# gpio_led.net
KiCad netlist of a schematic drawn in Altium Designer
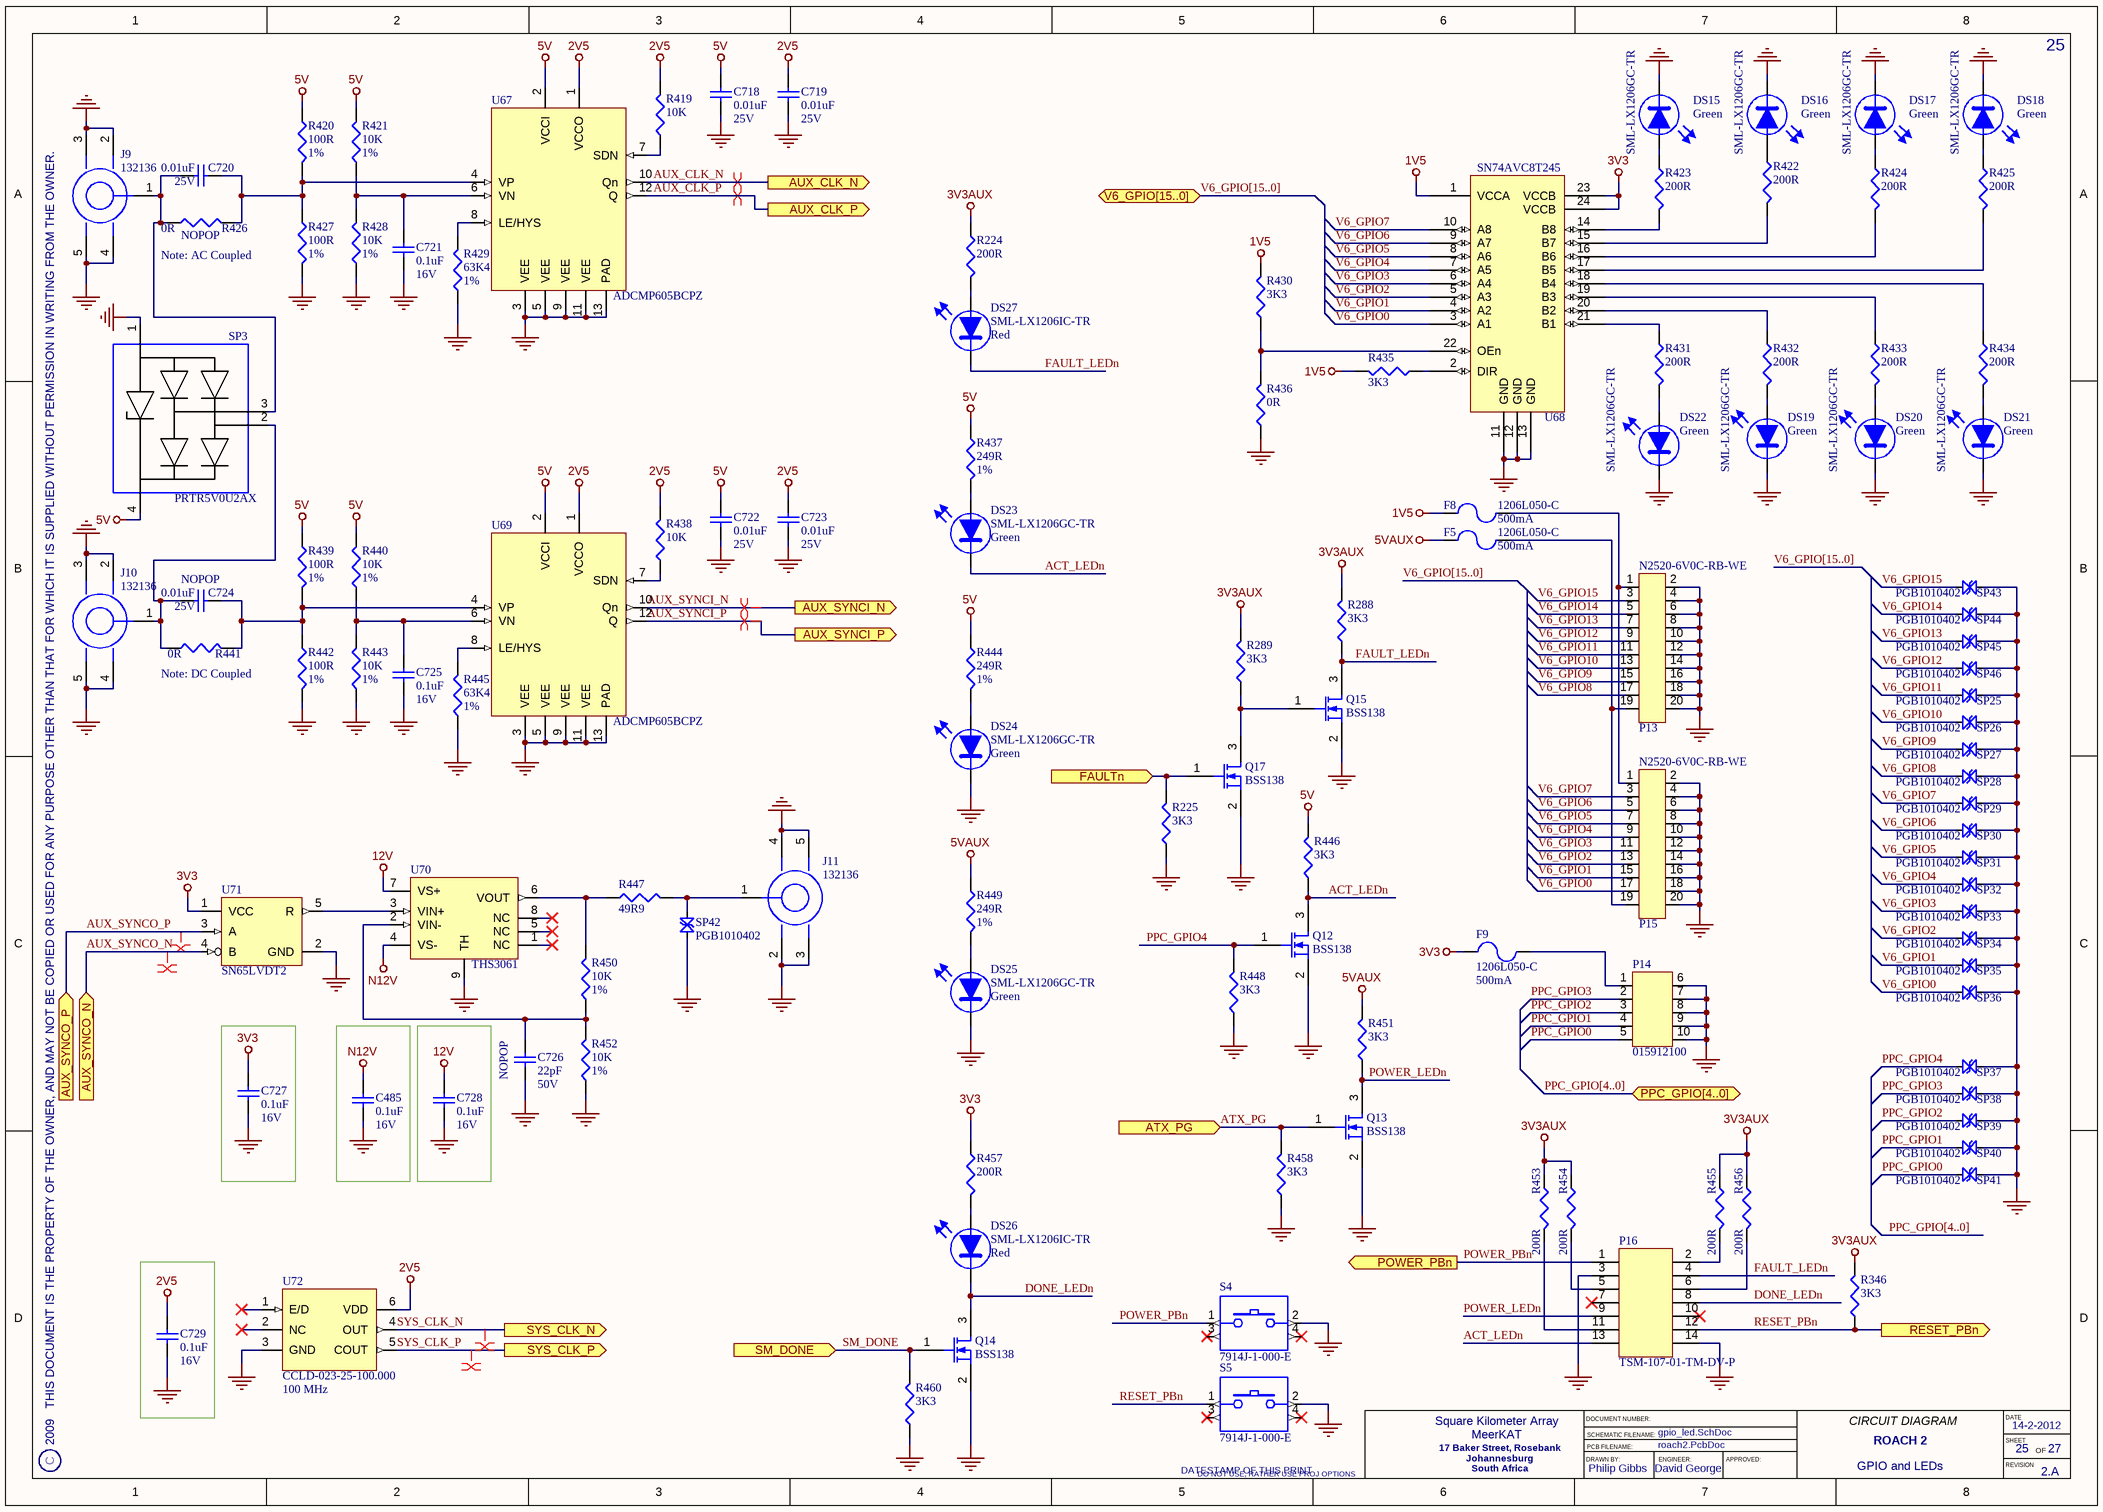
[diagram p0: gpio_led.SchDoc]

(export (version "E")
  (design (tool "Eeschema 10.0.6"))
  (components
    (comp (ref "C485")
      (value "0.1uF")
      (footprint "CAPC1005X60L")
      (description "0.1uF, Ceramic Capacitor")
      (fields
        (field (name "RATING") "16V")
        (field (name "MANUFACTURER") "VENKEL")
        (field (name "PARTNUM") "C0402X7R160-104KN")
      )
      (libsource (lib "altium_db") (part "CapStd"))
    )
    (comp (ref "C718")
      (value "0.01uF")
      (footprint "CAPC1005X55L")
      (description "0.01uF, Ceramic Capacitor")
      (fields
        (field (name "RATING") "25V")
        (field (name "MANUFACTURER") "MURATA")
        (field (name "PARTNUM") "GRM155R71E103KA01D")
      )
      (libsource (lib "altium_db") (part "CapStd"))
    )
    (comp (ref "C719")
      (value "0.01uF")
      (footprint "CAPC1005X55L")
      (description "0.01uF, Ceramic Capacitor")
      (fields
        (field (name "RATING") "25V")
        (field (name "MANUFACTURER") "MURATA")
        (field (name "PARTNUM") "GRM155R71E103KA01D")
      )
      (libsource (lib "altium_db") (part "CapStd"))
    )
    (comp (ref "C720")
      (value "0.01uF")
      (footprint "CAPC1005X55L")
      (description "0.01uF, Ceramic Capacitor")
      (fields
        (field (name "RATING") "25V")
        (field (name "MANUFACTURER") "MURATA")
        (field (name "PARTNUM") "GRM155R71E103KA01D")
      )
      (libsource (lib "altium_db") (part "CapStd"))
    )
    (comp (ref "C721")
      (value "0.1uF")
      (footprint "CAPC1005X60L")
      (description "0.1uF, Ceramic Capacitor")
      (fields
        (field (name "RATING") "16V")
        (field (name "MANUFACTURER") "VENKEL")
        (field (name "PARTNUM") "C0402X7R160-104KN")
      )
      (libsource (lib "altium_db") (part "CapStd"))
    )
    (comp (ref "C722")
      (value "0.01uF")
      (footprint "CAPC1005X55L")
      (description "0.01uF, Ceramic Capacitor")
      (fields
        (field (name "RATING") "25V")
        (field (name "MANUFACTURER") "MURATA")
        (field (name "PARTNUM") "GRM155R71E103KA01D")
      )
      (libsource (lib "altium_db") (part "CapStd"))
    )
    (comp (ref "C723")
      (value "0.01uF")
      (footprint "CAPC1005X55L")
      (description "0.01uF, Ceramic Capacitor")
      (fields
        (field (name "RATING") "25V")
        (field (name "MANUFACTURER") "MURATA")
        (field (name "PARTNUM") "GRM155R71E103KA01D")
      )
      (libsource (lib "altium_db") (part "CapStd"))
    )
    (comp (ref "C724")
      (value "0.01uF")
      (footprint "CAPC1005X55L")
      (description "0.01uF, Ceramic Capacitor")
      (fields
        (field (name "RATING") "25V")
        (field (name "MANUFACTURER") "MURATA")
        (field (name "PARTNUM") "GRM155R71E103KA01D")
      )
      (libsource (lib "altium_db") (part "CapStd"))
    )
    (comp (ref "C725")
      (value "0.1uF")
      (footprint "CAPC1005X60L")
      (description "0.1uF, Ceramic Capacitor")
      (fields
        (field (name "RATING") "16V")
        (field (name "MANUFACTURER") "VENKEL")
        (field (name "PARTNUM") "C0402X7R160-104KN")
      )
      (libsource (lib "altium_db") (part "CapStd"))
    )
    (comp (ref "C726")
      (value "22pF")
      (footprint "CAPC1005X55L")
      (description "22pF, Ceramic Capacitor")
      (fields
        (field (name "RATING") "50V")
        (field (name "MANUFACTURER") "MURATA")
        (field (name "PARTNUM") "GRM1555C1H220JZ01D")
      )
      (libsource (lib "altium_db") (part "CapStd"))
    )
    (comp (ref "C727")
      (value "0.1uF")
      (footprint "CAPC1005X60L")
      (description "0.1uF, Ceramic Capacitor")
      (fields
        (field (name "RATING") "16V")
        (field (name "MANUFACTURER") "VENKEL")
        (field (name "PARTNUM") "C0402X7R160-104KN")
      )
      (libsource (lib "altium_db") (part "CapStd"))
    )
    (comp (ref "C728")
      (value "0.1uF")
      (footprint "CAPC1005X60L")
      (description "0.1uF, Ceramic Capacitor")
      (fields
        (field (name "RATING") "16V")
        (field (name "MANUFACTURER") "VENKEL")
        (field (name "PARTNUM") "C0402X7R160-104KN")
      )
      (libsource (lib "altium_db") (part "CapStd"))
    )
    (comp (ref "C729")
      (value "0.1uF")
      (footprint "CAPC1005X60L")
      (description "0.1uF, Ceramic Capacitor")
      (fields
        (field (name "RATING") "16V")
        (field (name "MANUFACTURER") "VENKEL")
        (field (name "PARTNUM") "C0402X7R160-104KN")
      )
      (libsource (lib "altium_db") (part "CapStd"))
    )
    (comp (ref "DS15")
      (value "SML-LX1206GC-TR")
      (footprint "LEDC3216X120N")
      (description "Green, Surface mount, LED, 1206")
      (fields (field (name "COLOUR") "Green") (field (name "MANUFACTURER") "LUMEX"))
      (libsource (lib "altium_db") (part "LEDSTD"))
    )
    (comp (ref "DS16")
      (value "SML-LX1206GC-TR")
      (footprint "LEDC3216X120N")
      (description "Green, Surface mount, LED, 1206")
      (fields (field (name "COLOUR") "Green") (field (name "MANUFACTURER") "LUMEX"))
      (libsource (lib "altium_db") (part "LEDSTD"))
    )
    (comp (ref "DS17")
      (value "SML-LX1206GC-TR")
      (footprint "LEDC3216X120N")
      (description "Green, Surface mount, LED, 1206")
      (fields (field (name "COLOUR") "Green") (field (name "MANUFACTURER") "LUMEX"))
      (libsource (lib "altium_db") (part "LEDSTD"))
    )
    (comp (ref "DS18")
      (value "SML-LX1206GC-TR")
      (footprint "LEDC3216X120N")
      (description "Green, Surface mount, LED, 1206")
      (fields (field (name "COLOUR") "Green") (field (name "MANUFACTURER") "LUMEX"))
      (libsource (lib "altium_db") (part "LEDSTD"))
    )
    (comp (ref "DS19")
      (value "SML-LX1206GC-TR")
      (footprint "LEDC3216X120N")
      (description "Green, Surface mount, LED, 1206")
      (fields (field (name "COLOUR") "Green") (field (name "MANUFACTURER") "LUMEX"))
      (libsource (lib "altium_db") (part "LEDSTD"))
    )
    (comp (ref "DS20")
      (value "SML-LX1206GC-TR")
      (footprint "LEDC3216X120N")
      (description "Green, Surface mount, LED, 1206")
      (fields (field (name "COLOUR") "Green") (field (name "MANUFACTURER") "LUMEX"))
      (libsource (lib "altium_db") (part "LEDSTD"))
    )
    (comp (ref "DS21")
      (value "SML-LX1206GC-TR")
      (footprint "LEDC3216X120N")
      (description "Green, Surface mount, LED, 1206")
      (fields (field (name "COLOUR") "Green") (field (name "MANUFACTURER") "LUMEX"))
      (libsource (lib "altium_db") (part "LEDSTD"))
    )
    (comp (ref "DS22")
      (value "SML-LX1206GC-TR")
      (footprint "LEDC3216X120N")
      (description "Green, Surface mount, LED, 1206")
      (fields (field (name "COLOUR") "Green") (field (name "MANUFACTURER") "LUMEX"))
      (libsource (lib "altium_db") (part "LEDSTD"))
    )
    (comp (ref "DS23")
      (value "SML-LX1206GC-TR")
      (footprint "LEDC3216X120N")
      (description "Green, Surface mount, LED, 1206")
      (fields (field (name "COLOUR") "Green") (field (name "MANUFACTURER") "LUMEX"))
      (libsource (lib "altium_db") (part "LEDSTD"))
    )
    (comp (ref "DS24")
      (value "SML-LX1206GC-TR")
      (footprint "LEDC3216X120N")
      (description "Green, Surface mount, LED, 1206")
      (fields (field (name "COLOUR") "Green") (field (name "MANUFACTURER") "LUMEX"))
      (libsource (lib "altium_db") (part "LEDSTD"))
    )
    (comp (ref "DS25")
      (value "SML-LX1206GC-TR")
      (footprint "LEDC3216X120N")
      (description "Green, Surface mount, LED, 1206")
      (fields (field (name "COLOUR") "Green") (field (name "MANUFACTURER") "LUMEX"))
      (libsource (lib "altium_db") (part "LEDSTD"))
    )
    (comp (ref "DS26")
      (value "SML-LX1206IC-TR")
      (footprint "LEDC3216X120N")
      (description "Red, Surface mount, LED, 1206")
      (fields (field (name "COLOUR") "Red") (field (name "MANUFACTURER") "LUMEX"))
      (libsource (lib "altium_db") (part "LEDSTD"))
    )
    (comp (ref "DS27")
      (value "SML-LX1206IC-TR")
      (footprint "LEDC3216X120N")
      (description "Red, Surface mount, LED, 1206")
      (fields (field (name "COLOUR") "Red") (field (name "MANUFACTURER") "LUMEX"))
      (libsource (lib "altium_db") (part "LEDSTD"))
    )
    (comp (ref "F5")
      (value "1206L050-C")
      (footprint "FUSMC3215X145")
      (description "Resettable, Surface mount Fuse")
      (fields
        (field (name "PARTNUM") "1206L050-C")
        (field (name "MANUFACTURER") "Littelfuse")
        (field (name "RATING") "500mA")
      )
      (libsource (lib "altium_db") (part "FuseStd"))
    )
    (comp (ref "F8")
      (value "1206L050-C")
      (footprint "FUSMC3215X145")
      (description "Resettable, Surface mount Fuse")
      (fields
        (field (name "PARTNUM") "1206L050-C")
        (field (name "MANUFACTURER") "Littelfuse")
        (field (name "RATING") "500mA")
      )
      (libsource (lib "altium_db") (part "FuseStd"))
    )
    (comp (ref "F9")
      (value "1206L050-C")
      (footprint "FUSMC3215X145")
      (description "Resettable, Surface mount Fuse")
      (fields
        (field (name "PARTNUM") "1206L050-C")
        (field (name "MANUFACTURER") "Littelfuse")
        (field (name "RATING") "500mA")
      )
      (libsource (lib "altium_db") (part "FuseStd"))
    )
    (comp (ref "J9")
      (value "132136")
      (footprint "AMPHENOL_132134")
      (description "PCB-Mounted, Vertical, SMA Connector")
      (fields (field (name "PARTNUM") "132136") (field (name "MANUFACTURER") "Amphenol"))
      (libsource (lib "altium_db") (part "SMA_PCBMOUNT"))
    )
    (comp (ref "J10")
      (value "132136")
      (footprint "AMPHENOL_132134")
      (description "PCB-Mounted, Vertical, SMA Connector")
      (fields (field (name "PARTNUM") "132136") (field (name "MANUFACTURER") "Amphenol"))
      (libsource (lib "altium_db") (part "SMA_PCBMOUNT"))
    )
    (comp (ref "J11")
      (value "132136")
      (footprint "AMPHENOL_132134")
      (description "PCB-Mounted, Vertical, SMA Connector")
      (fields (field (name "PARTNUM") "132136") (field (name "MANUFACTURER") "Amphenol"))
      (libsource (lib "altium_db") (part "SMA_PCBMOUNT"))
    )
    (comp (ref "P13")
      (value "N2520-6V0C-RB-WE")
      (footprint "3M_N2520-6V0C-RB-WE")
      (description "2x10, 2.54mm Pitch, Male Shrouded Header")
      (fields (field (name "PARTNUM") "N2520-6V0C-RB-WE") (field (name "MANUFACTURER") "3M"))
      (libsource (lib "altium_db") (part "con_hdr_2x10_shr"))
    )
    (comp (ref "P14")
      (value "015912100")
      (footprint "MOLEX_0015912100")
      (description "2x5, 2.54 mm Pitch, Male Header")
      (fields (field (name "PARTNUM") "015912100") (field (name "MANUFACTURER") "Molex"))
      (libsource (lib "altium_db") (part "con_hdr_2x5"))
    )
    (comp (ref "P15")
      (value "N2520-6V0C-RB-WE")
      (footprint "3M_N2520-6V0C-RB-WE")
      (description "2x10, 2.54mm Pitch, Male Shrouded Header")
      (fields (field (name "PARTNUM") "N2520-6V0C-RB-WE") (field (name "MANUFACTURER") "3M"))
      (libsource (lib "altium_db") (part "con_hdr_2x10_shr"))
    )
    (comp (ref "P16")
      (value "TSM-107-01-TM-DV-P")
      (footprint "SAMTEC_TSM-107-01-TM-DV-P")
      (description "2x7, 2.54 mm Pitch, Male Header")
      (fields (field (name "PARTNUM") "TSM-107-01-TM-DV-P") (field (name "MANUFACTURER") "SAMTEC"))
      (libsource (lib "altium_db") (part "con_hdr_2x7"))
    )
    (comp (ref "Q12")
      (value "BSS138")
      (footprint "SOT95P245X110-3N")
      (description "N-Channel Logic Level Enhancement Mode Field Effect Transistor")
      (fields (field (name "MANUFACTURER") "Fairchild Semiconductor"))
      (libsource (lib "altium_db") (part "BSS138"))
    )
    (comp (ref "Q13")
      (value "BSS138")
      (footprint "SOT95P245X110-3N")
      (description "N-Channel Logic Level Enhancement Mode Field Effect Transistor")
      (fields (field (name "MANUFACTURER") "Fairchild Semiconductor"))
      (libsource (lib "altium_db") (part "BSS138"))
    )
    (comp (ref "Q14")
      (value "BSS138")
      (footprint "SOT95P245X110-3N")
      (description "N-Channel Logic Level Enhancement Mode Field Effect Transistor")
      (fields (field (name "MANUFACTURER") "Fairchild Semiconductor"))
      (libsource (lib "altium_db") (part "BSS138"))
    )
    (comp (ref "Q15")
      (value "BSS138")
      (footprint "SOT95P245X110-3N")
      (description "N-Channel Logic Level Enhancement Mode Field Effect Transistor")
      (fields (field (name "MANUFACTURER") "Fairchild Semiconductor"))
      (libsource (lib "altium_db") (part "BSS138"))
    )
    (comp (ref "Q17")
      (value "BSS138")
      (footprint "SOT95P245X110-3N")
      (description "N-Channel Logic Level Enhancement Mode Field Effect Transistor")
      (fields (field (name "MANUFACTURER") "Fairchild Semiconductor"))
      (libsource (lib "altium_db") (part "BSS138"))
    )
    (comp (ref "R224")
      (value "200R")
      (footprint "RESC1005X40L")
      (description "200R, 1.1mm x 0.5mm, Thick Film Resistor")
      (fields (field (name "MANUFACTURER") "ROYALOHM") (field (name "PARTNUM") "0402WGF0201T1E"))
      (libsource (lib "altium_db") (part "ResStd"))
    )
    (comp (ref "R225")
      (value "3K3")
      (footprint "RESC1005X40L")
      (description "3K3, 1.1mm x 0.5mm, Thick Film Resistor")
      (fields (field (name "MANUFACTURER") "ROYALOHM") (field (name "PARTNUM") "0402WGJ0332T1E"))
      (libsource (lib "altium_db") (part "ResStd"))
    )
    (comp (ref "R288")
      (value "3K3")
      (footprint "RESC1005X40L")
      (description "3K3, 1.1mm x 0.5mm, Thick Film Resistor")
      (fields (field (name "MANUFACTURER") "ROYALOHM") (field (name "PARTNUM") "0402WGJ0332T1E"))
      (libsource (lib "altium_db") (part "ResStd"))
    )
    (comp (ref "R289")
      (value "3K3")
      (footprint "RESC1005X40L")
      (description "3K3, 1.1mm x 0.5mm, Thick Film Resistor")
      (fields (field (name "MANUFACTURER") "ROYALOHM") (field (name "PARTNUM") "0402WGJ0332T1E"))
      (libsource (lib "altium_db") (part "ResStd"))
    )
    (comp (ref "R346")
      (value "3K3")
      (footprint "RESC1005X40L")
      (description "3K3, 1.1mm x 0.5mm, Thick Film Resistor")
      (fields (field (name "MANUFACTURER") "ROYALOHM") (field (name "PARTNUM") "0402WGJ0332T1E"))
      (libsource (lib "altium_db") (part "ResStd"))
    )
    (comp (ref "R419")
      (value "10K")
      (footprint "RESC1005X40L")
      (description "10K, 1.1mm x 0.5mm, Thick Film Resistor")
      (fields (field (name "MANUFACTURER") "ROYALOHM") (field (name "PARTNUM") "0402WGJ0103T1E"))
      (libsource (lib "altium_db") (part "ResStd"))
    )
    (comp (ref "R420")
      (value "100R")
      (footprint "RESC1005X40L")
      (description "100R, 1.1mm x 0.5mm, Thick Film Resistor")
      (fields
        (field (name "MANUFACTURER") "ROYALOHM")
        (field (name "PARTNUM") "0402WGF0101T1E")
        (field (name "TOLERANCE") "1%")
      )
      (libsource (lib "altium_db") (part "ResStd"))
    )
    (comp (ref "R421")
      (value "10K")
      (footprint "RESC1005X40L")
      (description "10K, 1.1mm x 0.5mm, Thick Film Resistor")
      (fields
        (field (name "MANUFACTURER") "ROYALOHM")
        (field (name "PARTNUM") "0402WGF0103T1E")
        (field (name "TOLERANCE") "1%")
      )
      (libsource (lib "altium_db") (part "ResStd"))
    )
    (comp (ref "R422")
      (value "200R")
      (footprint "RESC1005X40L")
      (description "200R, 1.1mm x 0.5mm, Thick Film Resistor")
      (fields (field (name "MANUFACTURER") "ROYALOHM") (field (name "PARTNUM") "0402WGF0201T1E"))
      (libsource (lib "altium_db") (part "ResStd"))
    )
    (comp (ref "R423")
      (value "200R")
      (footprint "RESC1005X40L")
      (description "200R, 1.1mm x 0.5mm, Thick Film Resistor")
      (fields (field (name "MANUFACTURER") "ROYALOHM") (field (name "PARTNUM") "0402WGF0201T1E"))
      (libsource (lib "altium_db") (part "ResStd"))
    )
    (comp (ref "R424")
      (value "200R")
      (footprint "RESC1005X40L")
      (description "200R, 1.1mm x 0.5mm, Thick Film Resistor")
      (fields (field (name "MANUFACTURER") "ROYALOHM") (field (name "PARTNUM") "0402WGF0201T1E"))
      (libsource (lib "altium_db") (part "ResStd"))
    )
    (comp (ref "R425")
      (value "200R")
      (footprint "RESC1005X40L")
      (description "200R, 1.1mm x 0.5mm, Thick Film Resistor")
      (fields (field (name "MANUFACTURER") "ROYALOHM") (field (name "PARTNUM") "0402WGF0201T1E"))
      (libsource (lib "altium_db") (part "ResStd"))
    )
    (comp (ref "R426")
      (value "0R")
      (footprint "RESC1005X40L")
      (description "0R, 1.1mm x 0.5mm, Thick Film Resistor")
      (fields (field (name "MANUFACTURER") "ROYALOHM") (field (name "PARTNUM") "0402WG00000T1E"))
      (libsource (lib "altium_db") (part "ResStd"))
    )
    (comp (ref "R427")
      (value "100R")
      (footprint "RESC1005X40L")
      (description "100R, 1.1mm x 0.5mm, Thick Film Resistor")
      (fields
        (field (name "MANUFACTURER") "ROYALOHM")
        (field (name "PARTNUM") "0402WGF0101T1E")
        (field (name "TOLERANCE") "1%")
      )
      (libsource (lib "altium_db") (part "ResStd"))
    )
    (comp (ref "R428")
      (value "10K")
      (footprint "RESC1005X40L")
      (description "10K, 1.1mm x 0.5mm, Thick Film Resistor")
      (fields
        (field (name "MANUFACTURER") "ROYALOHM")
        (field (name "PARTNUM") "0402WGF0103T1E")
        (field (name "TOLERANCE") "1%")
      )
      (libsource (lib "altium_db") (part "ResStd"))
    )
    (comp (ref "R429")
      (value "63K4")
      (footprint "RESC1005X40L")
      (description "63K4, 1.1mm x 0.5mm, Thick Film Resistor")
      (fields
        (field (name "MANUFACTURER") "ROYALOHM")
        (field (name "PARTNUM") "0402WGF6342T1E")
        (field (name "TOLERANCE") "1%")
      )
      (libsource (lib "altium_db") (part "ResStd"))
    )
    (comp (ref "R430")
      (value "3K3")
      (footprint "RESC1005X40L")
      (description "3K3, 1.1mm x 0.5mm, Thick Film Resistor")
      (fields (field (name "MANUFACTURER") "ROYALOHM") (field (name "PARTNUM") "0402WGJ0332T1E"))
      (libsource (lib "altium_db") (part "ResStd"))
    )
    (comp (ref "R431")
      (value "200R")
      (footprint "RESC1005X40L")
      (description "200R, 1.1mm x 0.5mm, Thick Film Resistor")
      (fields (field (name "MANUFACTURER") "ROYALOHM") (field (name "PARTNUM") "0402WGF0201T1E"))
      (libsource (lib "altium_db") (part "ResStd"))
    )
    (comp (ref "R432")
      (value "200R")
      (footprint "RESC1005X40L")
      (description "200R, 1.1mm x 0.5mm, Thick Film Resistor")
      (fields (field (name "MANUFACTURER") "ROYALOHM") (field (name "PARTNUM") "0402WGF0201T1E"))
      (libsource (lib "altium_db") (part "ResStd"))
    )
    (comp (ref "R433")
      (value "200R")
      (footprint "RESC1005X40L")
      (description "200R, 1.1mm x 0.5mm, Thick Film Resistor")
      (fields (field (name "MANUFACTURER") "ROYALOHM") (field (name "PARTNUM") "0402WGF0201T1E"))
      (libsource (lib "altium_db") (part "ResStd"))
    )
    (comp (ref "R434")
      (value "200R")
      (footprint "RESC1005X40L")
      (description "200R, 1.1mm x 0.5mm, Thick Film Resistor")
      (fields (field (name "MANUFACTURER") "ROYALOHM") (field (name "PARTNUM") "0402WGF0201T1E"))
      (libsource (lib "altium_db") (part "ResStd"))
    )
    (comp (ref "R435")
      (value "3K3")
      (footprint "RESC1005X40L")
      (description "3K3, 1.1mm x 0.5mm, Thick Film Resistor")
      (fields (field (name "MANUFACTURER") "ROYALOHM") (field (name "PARTNUM") "0402WGJ0332T1E"))
      (libsource (lib "altium_db") (part "ResStd"))
    )
    (comp (ref "R436")
      (value "0R")
      (footprint "RESC1005X40L")
      (description "0R, 1.1mm x 0.5mm, Thick Film Resistor")
      (fields (field (name "MANUFACTURER") "ROYALOHM") (field (name "PARTNUM") "0402WG00000T1E"))
      (libsource (lib "altium_db") (part "ResStd"))
    )
    (comp (ref "R437")
      (value "249R")
      (footprint "RESC1005X40L")
      (description "249R, 1.1mm x 0.5mm, Thick Film Resistor")
      (fields
        (field (name "MANUFACTURER") "ROYALOHM")
        (field (name "PARTNUM") "0402WGF2490T1E")
        (field (name "TOLERANCE") "1%")
      )
      (libsource (lib "altium_db") (part "ResStd"))
    )
    (comp (ref "R438")
      (value "10K")
      (footprint "RESC1005X40L")
      (description "10K, 1.1mm x 0.5mm, Thick Film Resistor")
      (fields (field (name "MANUFACTURER") "ROYALOHM") (field (name "PARTNUM") "0402WGJ0103T1E"))
      (libsource (lib "altium_db") (part "ResStd"))
    )
    (comp (ref "R439")
      (value "100R")
      (footprint "RESC1005X40L")
      (description "100R, 1.1mm x 0.5mm, Thick Film Resistor")
      (fields
        (field (name "MANUFACTURER") "ROYALOHM")
        (field (name "PARTNUM") "0402WGF0101T1E")
        (field (name "TOLERANCE") "1%")
      )
      (libsource (lib "altium_db") (part "ResStd"))
    )
    (comp (ref "R440")
      (value "10K")
      (footprint "RESC1005X40L")
      (description "10K, 1.1mm x 0.5mm, Thick Film Resistor")
      (fields
        (field (name "MANUFACTURER") "ROYALOHM")
        (field (name "PARTNUM") "0402WGF0103T1E")
        (field (name "TOLERANCE") "1%")
      )
      (libsource (lib "altium_db") (part "ResStd"))
    )
    (comp (ref "R441")
      (value "0R")
      (footprint "RESC1005X40L")
      (description "0R, 1.1mm x 0.5mm, Thick Film Resistor")
      (fields (field (name "MANUFACTURER") "ROYALOHM") (field (name "PARTNUM") "0402WG00000T1E"))
      (libsource (lib "altium_db") (part "ResStd"))
    )
    (comp (ref "R442")
      (value "100R")
      (footprint "RESC1005X40L")
      (description "100R, 1.1mm x 0.5mm, Thick Film Resistor")
      (fields
        (field (name "MANUFACTURER") "ROYALOHM")
        (field (name "PARTNUM") "0402WGF0101T1E")
        (field (name "TOLERANCE") "1%")
      )
      (libsource (lib "altium_db") (part "ResStd"))
    )
    (comp (ref "R443")
      (value "10K")
      (footprint "RESC1005X40L")
      (description "10K, 1.1mm x 0.5mm, Thick Film Resistor")
      (fields
        (field (name "MANUFACTURER") "ROYALOHM")
        (field (name "PARTNUM") "0402WGF0103T1E")
        (field (name "TOLERANCE") "1%")
      )
      (libsource (lib "altium_db") (part "ResStd"))
    )
    (comp (ref "R444")
      (value "249R")
      (footprint "RESC1005X40L")
      (description "249R, 1.1mm x 0.5mm, Thick Film Resistor")
      (fields
        (field (name "MANUFACTURER") "ROYALOHM")
        (field (name "PARTNUM") "0402WGF2490T1E")
        (field (name "TOLERANCE") "1%")
      )
      (libsource (lib "altium_db") (part "ResStd"))
    )
    (comp (ref "R445")
      (value "63K4")
      (footprint "RESC1005X40L")
      (description "63K4, 1.1mm x 0.5mm, Thick Film Resistor")
      (fields
        (field (name "MANUFACTURER") "ROYALOHM")
        (field (name "PARTNUM") "0402WGF6342T1E")
        (field (name "TOLERANCE") "1%")
      )
      (libsource (lib "altium_db") (part "ResStd"))
    )
    (comp (ref "R446")
      (value "3K3")
      (footprint "RESC1005X40L")
      (description "3K3, 1.1mm x 0.5mm, Thick Film Resistor")
      (fields (field (name "MANUFACTURER") "ROYALOHM") (field (name "PARTNUM") "0402WGJ0332T1E"))
      (libsource (lib "altium_db") (part "ResStd"))
    )
    (comp (ref "R447")
      (value "49R9")
      (footprint "RESC1005X40L")
      (description "49R9, 1.1mm x 0.5mm, Thick Film Resistor")
      (fields (field (name "MANUFACTURER") "ROYALOHM") (field (name "PARTNUM") "0402WGF499JT1E"))
      (libsource (lib "altium_db") (part "ResStd"))
    )
    (comp (ref "R448")
      (value "3K3")
      (footprint "RESC1005X40L")
      (description "3K3, 1.1mm x 0.5mm, Thick Film Resistor")
      (fields (field (name "MANUFACTURER") "ROYALOHM") (field (name "PARTNUM") "0402WGJ0332T1E"))
      (libsource (lib "altium_db") (part "ResStd"))
    )
    (comp (ref "R449")
      (value "249R")
      (footprint "RESC1005X40L")
      (description "249R, 1.1mm x 0.5mm, Thick Film Resistor")
      (fields
        (field (name "MANUFACTURER") "ROYALOHM")
        (field (name "PARTNUM") "0402WGF2490T1E")
        (field (name "TOLERANCE") "1%")
      )
      (libsource (lib "altium_db") (part "ResStd"))
    )
    (comp (ref "R450")
      (value "10K")
      (footprint "RESC1005X40L")
      (description "10K, 1.1mm x 0.5mm, Thick Film Resistor")
      (fields
        (field (name "MANUFACTURER") "ROYALOHM")
        (field (name "PARTNUM") "0402WGF0103T1E")
        (field (name "TOLERANCE") "1%")
      )
      (libsource (lib "altium_db") (part "ResStd"))
    )
    (comp (ref "R451")
      (value "3K3")
      (footprint "RESC1005X40L")
      (description "3K3, 1.1mm x 0.5mm, Thick Film Resistor")
      (fields (field (name "MANUFACTURER") "ROYALOHM") (field (name "PARTNUM") "0402WGJ0332T1E"))
      (libsource (lib "altium_db") (part "ResStd"))
    )
    (comp (ref "R452")
      (value "10K")
      (footprint "RESC1005X40L")
      (description "10K, 1.1mm x 0.5mm, Thick Film Resistor")
      (fields
        (field (name "MANUFACTURER") "ROYALOHM")
        (field (name "PARTNUM") "0402WGF0103T1E")
        (field (name "TOLERANCE") "1%")
      )
      (libsource (lib "altium_db") (part "ResStd"))
    )
    (comp (ref "R453")
      (value "200R")
      (footprint "RESC1005X40L")
      (description "200R, 1.1mm x 0.5mm, Thick Film Resistor")
      (fields (field (name "MANUFACTURER") "ROYALOHM") (field (name "PARTNUM") "0402WGF0201T1E"))
      (libsource (lib "altium_db") (part "ResStd"))
    )
    (comp (ref "R454")
      (value "200R")
      (footprint "RESC1005X40L")
      (description "200R, 1.1mm x 0.5mm, Thick Film Resistor")
      (fields (field (name "MANUFACTURER") "ROYALOHM") (field (name "PARTNUM") "0402WGF0201T1E"))
      (libsource (lib "altium_db") (part "ResStd"))
    )
    (comp (ref "R455")
      (value "200R")
      (footprint "RESC1005X40L")
      (description "200R, 1.1mm x 0.5mm, Thick Film Resistor")
      (fields (field (name "MANUFACTURER") "ROYALOHM") (field (name "PARTNUM") "0402WGF0201T1E"))
      (libsource (lib "altium_db") (part "ResStd"))
    )
    (comp (ref "R456")
      (value "200R")
      (footprint "RESC1005X40L")
      (description "200R, 1.1mm x 0.5mm, Thick Film Resistor")
      (fields (field (name "MANUFACTURER") "ROYALOHM") (field (name "PARTNUM") "0402WGF0201T1E"))
      (libsource (lib "altium_db") (part "ResStd"))
    )
    (comp (ref "R457")
      (value "200R")
      (footprint "RESC1005X40L")
      (description "200R, 1.1mm x 0.5mm, Thick Film Resistor")
      (fields (field (name "MANUFACTURER") "ROYALOHM") (field (name "PARTNUM") "0402WGF0201T1E"))
      (libsource (lib "altium_db") (part "ResStd"))
    )
    (comp (ref "R458")
      (value "3K3")
      (footprint "RESC1005X40L")
      (description "3K3, 1.1mm x 0.5mm, Thick Film Resistor")
      (fields (field (name "MANUFACTURER") "ROYALOHM") (field (name "PARTNUM") "0402WGJ0332T1E"))
      (libsource (lib "altium_db") (part "ResStd"))
    )
    (comp (ref "R460")
      (value "3K3")
      (footprint "RESC1005X40L")
      (description "3K3, 1.1mm x 0.5mm, Thick Film Resistor")
      (fields (field (name "MANUFACTURER") "ROYALOHM") (field (name "PARTNUM") "0402WGJ0332T1E"))
      (libsource (lib "altium_db") (part "ResStd"))
    )
    (comp (ref "S4")
      (value "7914J-1-000-E")
      (footprint "7914J-X-XXX-X")
      (description "4mm, Surface mount, Sealed Key Switch")
      (fields (field (name "PARTNUM") "7914J-1-000-E") (field (name "MANUFACTURER") "BOURNS"))
      (libsource (lib "altium_db") (part "7914X-X-XXX-X"))
    )
    (comp (ref "S5")
      (value "7914J-1-000-E")
      (footprint "7914J-X-XXX-X")
      (description "4mm, Surface mount, Sealed Key Switch")
      (fields (field (name "PARTNUM") "7914J-1-000-E") (field (name "MANUFACTURER") "BOURNS"))
      (libsource (lib "altium_db") (part "7914X-X-XXX-X"))
    )
    (comp (ref "SP3")
      (value "PRTR5V0U2AX")
      (footprint "SOT192P237X120-4N")
      (description "Ultra-low capacitance, double rail-to-rail, ESD protection diode in a SOT143B package")
      (fields (field (name "PARTNUM") "PRTR5V0U2AX") (field (name "MANUFACTURER") "NXP"))
      (libsource (lib "altium_db") (part "PRTR5V0U2AX"))
    )
    (comp (ref "SP25")
      (value "PGB1010402")
      (footprint "PGB1010402")
      (description "Surface Mount Polymeric ESD Suppressor in an 0402 package")
      (fields (field (name "PARTNUM") "PGB1010402"))
      (libsource (lib "altium_db") (part "PGB1010402"))
    )
    (comp (ref "SP26")
      (value "PGB1010402")
      (footprint "PGB1010402")
      (description "Surface Mount Polymeric ESD Suppressor in an 0402 package")
      (fields (field (name "PARTNUM") "PGB1010402"))
      (libsource (lib "altium_db") (part "PGB1010402"))
    )
    (comp (ref "SP27")
      (value "PGB1010402")
      (footprint "PGB1010402")
      (description "Surface Mount Polymeric ESD Suppressor in an 0402 package")
      (fields (field (name "PARTNUM") "PGB1010402"))
      (libsource (lib "altium_db") (part "PGB1010402"))
    )
    (comp (ref "SP28")
      (value "PGB1010402")
      (footprint "PGB1010402")
      (description "Surface Mount Polymeric ESD Suppressor in an 0402 package")
      (fields (field (name "PARTNUM") "PGB1010402"))
      (libsource (lib "altium_db") (part "PGB1010402"))
    )
    (comp (ref "SP29")
      (value "PGB1010402")
      (footprint "PGB1010402")
      (description "Surface Mount Polymeric ESD Suppressor in an 0402 package")
      (fields (field (name "PARTNUM") "PGB1010402"))
      (libsource (lib "altium_db") (part "PGB1010402"))
    )
    (comp (ref "SP30")
      (value "PGB1010402")
      (footprint "PGB1010402")
      (description "Surface Mount Polymeric ESD Suppressor in an 0402 package")
      (fields (field (name "PARTNUM") "PGB1010402"))
      (libsource (lib "altium_db") (part "PGB1010402"))
    )
    (comp (ref "SP31")
      (value "PGB1010402")
      (footprint "PGB1010402")
      (description "Surface Mount Polymeric ESD Suppressor in an 0402 package")
      (fields (field (name "PARTNUM") "PGB1010402"))
      (libsource (lib "altium_db") (part "PGB1010402"))
    )
    (comp (ref "SP32")
      (value "PGB1010402")
      (footprint "PGB1010402")
      (description "Surface Mount Polymeric ESD Suppressor in an 0402 package")
      (fields (field (name "PARTNUM") "PGB1010402"))
      (libsource (lib "altium_db") (part "PGB1010402"))
    )
    (comp (ref "SP33")
      (value "PGB1010402")
      (footprint "PGB1010402")
      (description "Surface Mount Polymeric ESD Suppressor in an 0402 package")
      (fields (field (name "PARTNUM") "PGB1010402"))
      (libsource (lib "altium_db") (part "PGB1010402"))
    )
    (comp (ref "SP34")
      (value "PGB1010402")
      (footprint "PGB1010402")
      (description "Surface Mount Polymeric ESD Suppressor in an 0402 package")
      (fields (field (name "PARTNUM") "PGB1010402"))
      (libsource (lib "altium_db") (part "PGB1010402"))
    )
    (comp (ref "SP35")
      (value "PGB1010402")
      (footprint "PGB1010402")
      (description "Surface Mount Polymeric ESD Suppressor in an 0402 package")
      (fields (field (name "PARTNUM") "PGB1010402"))
      (libsource (lib "altium_db") (part "PGB1010402"))
    )
    (comp (ref "SP36")
      (value "PGB1010402")
      (footprint "PGB1010402")
      (description "Surface Mount Polymeric ESD Suppressor in an 0402 package")
      (fields (field (name "PARTNUM") "PGB1010402"))
      (libsource (lib "altium_db") (part "PGB1010402"))
    )
    (comp (ref "SP37")
      (value "PGB1010402")
      (footprint "PGB1010402")
      (description "Surface Mount Polymeric ESD Suppressor in an 0402 package")
      (fields (field (name "PARTNUM") "PGB1010402"))
      (libsource (lib "altium_db") (part "PGB1010402"))
    )
    (comp (ref "SP38")
      (value "PGB1010402")
      (footprint "PGB1010402")
      (description "Surface Mount Polymeric ESD Suppressor in an 0402 package")
      (fields (field (name "PARTNUM") "PGB1010402"))
      (libsource (lib "altium_db") (part "PGB1010402"))
    )
    (comp (ref "SP39")
      (value "PGB1010402")
      (footprint "PGB1010402")
      (description "Surface Mount Polymeric ESD Suppressor in an 0402 package")
      (fields (field (name "PARTNUM") "PGB1010402"))
      (libsource (lib "altium_db") (part "PGB1010402"))
    )
    (comp (ref "SP40")
      (value "PGB1010402")
      (footprint "PGB1010402")
      (description "Surface Mount Polymeric ESD Suppressor in an 0402 package")
      (fields (field (name "PARTNUM") "PGB1010402"))
      (libsource (lib "altium_db") (part "PGB1010402"))
    )
    (comp (ref "SP41")
      (value "PGB1010402")
      (footprint "PGB1010402")
      (description "Surface Mount Polymeric ESD Suppressor in an 0402 package")
      (fields (field (name "PARTNUM") "PGB1010402"))
      (libsource (lib "altium_db") (part "PGB1010402"))
    )
    (comp (ref "SP42")
      (value "PGB1010402")
      (footprint "PGB1010402")
      (description "Surface Mount Polymeric ESD Suppressor in an 0402 package")
      (fields (field (name "PARTNUM") "PGB1010402"))
      (libsource (lib "altium_db") (part "PGB1010402"))
    )
    (comp (ref "SP43")
      (value "PGB1010402")
      (footprint "PGB1010402")
      (description "Surface Mount Polymeric ESD Suppressor in an 0402 package")
      (fields (field (name "PARTNUM") "PGB1010402"))
      (libsource (lib "altium_db") (part "PGB1010402"))
    )
    (comp (ref "SP44")
      (value "PGB1010402")
      (footprint "PGB1010402")
      (description "Surface Mount Polymeric ESD Suppressor in an 0402 package")
      (fields (field (name "PARTNUM") "PGB1010402"))
      (libsource (lib "altium_db") (part "PGB1010402"))
    )
    (comp (ref "SP45")
      (value "PGB1010402")
      (footprint "PGB1010402")
      (description "Surface Mount Polymeric ESD Suppressor in an 0402 package")
      (fields (field (name "PARTNUM") "PGB1010402"))
      (libsource (lib "altium_db") (part "PGB1010402"))
    )
    (comp (ref "SP46")
      (value "PGB1010402")
      (footprint "PGB1010402")
      (description "Surface Mount Polymeric ESD Suppressor in an 0402 package")
      (fields (field (name "PARTNUM") "PGB1010402"))
      (libsource (lib "altium_db") (part "PGB1010402"))
    )
    (comp (ref "U67")
      (value "ADCMP605BCPZ")
      (footprint "LFCSP_VQ-12")
      (description "Rail-to-Rail, Very Fast, 2.5 V to 5.5 V, Single-Supply LVDS Comparators")
      (fields (field (name "MANUFACTURER") "Analog Devices"))
      (libsource (lib "altium_db") (part "ADCMP605"))
    )
    (comp (ref "U68")
      (value "SN74AVC8T245")
      (footprint "PW024")
      (description "8-BIT DUAL-SUPPLY BUS TRANSCEIVER  WITH CONFIGURABLE VOLTAGE TRANSLATION AND 3-STATE OUTPUTS")
      (fields (field (name "MANUFACTURER") "Texas Instruments"))
      (libsource (lib "altium_db") (part "SN74AVC8T245"))
    )
    (comp (ref "U69")
      (value "ADCMP605BCPZ")
      (footprint "LFCSP_VQ-12")
      (description "Rail-to-Rail, Very Fast, 2.5 V to 5.5 V, Single-Supply LVDS Comparators")
      (fields (field (name "MANUFACTURER") "Analog Devices"))
      (libsource (lib "altium_db") (part "ADCMP605"))
    )
    (comp (ref "U70")
      (value "THS3061")
      (footprint "PW08")
      (description "LOW-DISTORTION, HIGH SLEW RATE, CURRENT-FEEDBACK AMPLIFIERS")
      (fields (field (name "MANUFACTURER") "Texas Instruments") (field (name "PARTNUM") "THS3061DGN"))
      (libsource (lib "altium_db") (part "THS3061"))
    )
    (comp (ref "U71")
      (value "SN65LVDT2")
      (footprint "SOT23-5")
      (description "Single High-Speed Differential Line Receiver with ODT")
      (fields (field (name "MANUFACTURER") "Texas Instruments"))
      (libsource (lib "altium_db") (part "SN65LVDT2"))
    )
    (comp (ref "U72")
      (value "CCLD-023-25-100.000")
      (footprint "CCLD-023X-XX-XXX_XXX")
      (description "100.00 MHz, Low-Jitter Differential LVDS Clock Oscillator")
      (fields
        (field (name "PARTNUM") "CCLD-023-25-100.000")
        (field (name "FREQUENCY") "100 MHz")
        (field (name "MANUFACTURER") "Crystek")
      )
      (libsource (lib "altium_db") (part "CCLD-023X-XX-XXX_XXX"))
    )
  )
  (nets
    (net (code "1") (name "/ACT_LEDn") (class "Default")
      (node (ref "DS23") (pin "1") (pinfunction "K_1") (pintype "passive"))
      (node (ref "P16") (pin "13") (pinfunction "13_13") (pintype "passive"))
      (node (ref "Q12") (pin "3") (pinfunction "D_3") (pintype "passive"))
      (node (ref "R446") (pin "1") (pinfunction "1_1") (pintype "passive"))
    )
    (net (code "2") (name "/ATX_PG") (class "Default")
      (node (ref "Q13") (pin "1") (pinfunction "G_1") (pintype "passive"))
      (node (ref "R458") (pin "2") (pinfunction "2_2") (pintype "passive"))
    )
    (net (code "3") (name "/AUX_CLK_N") (class "Default")
      (node (ref "U67") (pin "10") (pinfunction "Qn_10") (pintype "output"))
    )
    (net (code "4") (name "/AUX_CLK_P") (class "Default")
      (node (ref "U67") (pin "12") (pinfunction "Q_12") (pintype "output"))
    )
    (net (code "5") (name "/AUX_SYNCI_N") (class "Default")
      (node (ref "U69") (pin "10") (pinfunction "Qn_10") (pintype "output"))
    )
    (net (code "6") (name "/AUX_SYNCI_P") (class "Default")
      (node (ref "U69") (pin "12") (pinfunction "Q_12") (pintype "output"))
    )
    (net (code "7") (name "/AUX_SYNCO_N") (class "Default")
      (node (ref "U71") (pin "4") (pinfunction "B_4") (pintype "input"))
    )
    (net (code "8") (name "/AUX_SYNCO_P") (class "Default")
      (node (ref "U71") (pin "3") (pinfunction "A_3") (pintype "input"))
    )
    (net (code "9") (name "/DONE_LEDn") (class "Default")
      (node (ref "DS26") (pin "1") (pinfunction "K_1") (pintype "passive"))
      (node (ref "P16") (pin "8") (pinfunction "8_8") (pintype "passive"))
      (node (ref "Q14") (pin "3") (pinfunction "D_3") (pintype "passive"))
    )
    (net (code "10") (name "/FAULT_LEDn") (class "Default")
      (node (ref "DS27") (pin "1") (pinfunction "K_1") (pintype "passive"))
      (node (ref "P16") (pin "4") (pinfunction "4_4") (pintype "passive"))
      (node (ref "Q15") (pin "3") (pinfunction "D_3") (pintype "passive"))
      (node (ref "R288") (pin "1") (pinfunction "1_1") (pintype "passive"))
    )
    (net (code "11") (name "/FAULTn") (class "Default")
      (node (ref "Q17") (pin "1") (pinfunction "G_1") (pintype "passive"))
      (node (ref "R225") (pin "2") (pinfunction "2_2") (pintype "passive"))
    )
    (net (code "12") (name "/POWER_LEDn") (class "Default")
      (node (ref "P16") (pin "9") (pinfunction "9_9") (pintype "passive"))
      (node (ref "Q13") (pin "3") (pinfunction "D_3") (pintype "passive"))
      (node (ref "R451") (pin "1") (pinfunction "1_1") (pintype "passive"))
    )
    (net (code "13") (name "/POWER_PBn") (class "Default")
      (node (ref "P16") (pin "1") (pinfunction "1_1") (pintype "passive"))
      (node (ref "S4") (pin "1") (pinfunction "1_1") (pintype "output"))
    )
    (net (code "14") (name "/PPC_GPIO0") (class "Default")
      (node (ref "P14") (pin "5") (pinfunction "5_5") (pintype "passive"))
      (node (ref "SP41") (pin "2") (pinfunction "B_2") (pintype "passive"))
    )
    (net (code "15") (name "/PPC_GPIO1") (class "Default")
      (node (ref "P14") (pin "4") (pinfunction "4_4") (pintype "passive"))
      (node (ref "SP40") (pin "2") (pinfunction "B_2") (pintype "passive"))
    )
    (net (code "16") (name "/PPC_GPIO2") (class "Default")
      (node (ref "P14") (pin "3") (pinfunction "3_3") (pintype "passive"))
      (node (ref "SP39") (pin "2") (pinfunction "B_2") (pintype "passive"))
    )
    (net (code "17") (name "/PPC_GPIO3") (class "Default")
      (node (ref "P14") (pin "2") (pinfunction "2_2") (pintype "passive"))
      (node (ref "SP38") (pin "2") (pinfunction "B_2") (pintype "passive"))
    )
    (net (code "18") (name "/PPC_GPIO4") (class "Default")
      (node (ref "Q12") (pin "1") (pinfunction "G_1") (pintype "passive"))
      (node (ref "R448") (pin "2") (pinfunction "2_2") (pintype "passive"))
      (node (ref "SP37") (pin "2") (pinfunction "B_2") (pintype "passive"))
    )
    (net (code "20") (name "/RESET_PBn") (class "Default")
      (node (ref "P16") (pin "12") (pinfunction "12_12") (pintype "passive"))
      (node (ref "R346") (pin "1") (pinfunction "1_1") (pintype "passive"))
      (node (ref "S5") (pin "1") (pinfunction "1_1") (pintype "output"))
    )
    (net (code "21") (name "/SM_DONE") (class "Default")
      (node (ref "Q14") (pin "1") (pinfunction "G_1") (pintype "passive"))
      (node (ref "R460") (pin "2") (pinfunction "2_2") (pintype "passive"))
    )
    (net (code "22") (name "/SYS_CLK_N") (class "Default")
      (node (ref "U72") (pin "4") (pinfunction "OUT_4") (pintype "output"))
    )
    (net (code "23") (name "/SYS_CLK_P") (class "Default")
      (node (ref "U72") (pin "5") (pinfunction "COUT_5") (pintype "output"))
    )
    (net (code "24") (name "/V6_GPIO0") (class "Default")
      (node (ref "P15") (pin "17") (pinfunction "17_17") (pintype "passive"))
      (node (ref "SP36") (pin "2") (pinfunction "B_2") (pintype "passive"))
      (node (ref "U68") (pin "3") (pinfunction "A1_3") (pintype "bidirectional"))
    )
    (net (code "25") (name "/V6_GPIO1") (class "Default")
      (node (ref "P15") (pin "15") (pinfunction "15_15") (pintype "passive"))
      (node (ref "SP35") (pin "2") (pinfunction "B_2") (pintype "passive"))
      (node (ref "U68") (pin "4") (pinfunction "A2_4") (pintype "bidirectional"))
    )
    (net (code "26") (name "/V6_GPIO2") (class "Default")
      (node (ref "P15") (pin "13") (pinfunction "13_13") (pintype "passive"))
      (node (ref "SP34") (pin "2") (pinfunction "B_2") (pintype "passive"))
      (node (ref "U68") (pin "5") (pinfunction "A3_5") (pintype "bidirectional"))
    )
    (net (code "27") (name "/V6_GPIO3") (class "Default")
      (node (ref "P15") (pin "11") (pinfunction "11_11") (pintype "passive"))
      (node (ref "SP33") (pin "2") (pinfunction "B_2") (pintype "passive"))
      (node (ref "U68") (pin "6") (pinfunction "A4_6") (pintype "bidirectional"))
    )
    (net (code "28") (name "/V6_GPIO4") (class "Default")
      (node (ref "P15") (pin "9") (pinfunction "9_9") (pintype "passive"))
      (node (ref "SP32") (pin "2") (pinfunction "B_2") (pintype "passive"))
      (node (ref "U68") (pin "7") (pinfunction "A5_7") (pintype "bidirectional"))
    )
    (net (code "29") (name "/V6_GPIO5") (class "Default")
      (node (ref "P15") (pin "7") (pinfunction "7_7") (pintype "passive"))
      (node (ref "SP31") (pin "2") (pinfunction "B_2") (pintype "passive"))
      (node (ref "U68") (pin "8") (pinfunction "A6_8") (pintype "bidirectional"))
    )
    (net (code "30") (name "/V6_GPIO6") (class "Default")
      (node (ref "P15") (pin "5") (pinfunction "5_5") (pintype "passive"))
      (node (ref "SP30") (pin "2") (pinfunction "B_2") (pintype "passive"))
      (node (ref "U68") (pin "9") (pinfunction "A7_9") (pintype "bidirectional"))
    )
    (net (code "31") (name "/V6_GPIO7") (class "Default")
      (node (ref "P15") (pin "3") (pinfunction "3_3") (pintype "passive"))
      (node (ref "SP29") (pin "2") (pinfunction "B_2") (pintype "passive"))
      (node (ref "U68") (pin "10") (pinfunction "A8_10") (pintype "bidirectional"))
    )
    (net (code "32") (name "/V6_GPIO8") (class "Default")
      (node (ref "P13") (pin "17") (pinfunction "17_17") (pintype "passive"))
      (node (ref "SP28") (pin "2") (pinfunction "B_2") (pintype "passive"))
    )
    (net (code "33") (name "/V6_GPIO9") (class "Default")
      (node (ref "P13") (pin "15") (pinfunction "15_15") (pintype "passive"))
      (node (ref "SP27") (pin "2") (pinfunction "B_2") (pintype "passive"))
    )
    (net (code "34") (name "/V6_GPIO10") (class "Default")
      (node (ref "P13") (pin "13") (pinfunction "13_13") (pintype "passive"))
      (node (ref "SP26") (pin "2") (pinfunction "B_2") (pintype "passive"))
    )
    (net (code "35") (name "/V6_GPIO11") (class "Default")
      (node (ref "P13") (pin "11") (pinfunction "11_11") (pintype "passive"))
      (node (ref "SP25") (pin "2") (pinfunction "B_2") (pintype "passive"))
    )
    (net (code "36") (name "/V6_GPIO12") (class "Default")
      (node (ref "P13") (pin "9") (pinfunction "9_9") (pintype "passive"))
      (node (ref "SP46") (pin "2") (pinfunction "B_2") (pintype "passive"))
    )
    (net (code "37") (name "/V6_GPIO13") (class "Default")
      (node (ref "P13") (pin "7") (pinfunction "7_7") (pintype "passive"))
      (node (ref "SP45") (pin "2") (pinfunction "B_2") (pintype "passive"))
    )
    (net (code "38") (name "/V6_GPIO14") (class "Default")
      (node (ref "P13") (pin "5") (pinfunction "5_5") (pintype "passive"))
      (node (ref "SP44") (pin "2") (pinfunction "B_2") (pintype "passive"))
    )
    (net (code "39") (name "/V6_GPIO15") (class "Default")
      (node (ref "P13") (pin "3") (pinfunction "3_3") (pintype "passive"))
      (node (ref "SP43") (pin "2") (pinfunction "B_2") (pintype "passive"))
    )
    (net (code "41") (name "1V5") (class "Default")
      (node (ref "F8") (pin "1") (pinfunction "1_1") (pintype "passive"))
      (node (ref "R430") (pin "2") (pinfunction "2_2") (pintype "passive"))
      (node (ref "R435") (pin "2") (pinfunction "2_2") (pintype "passive"))
      (node (ref "U68") (pin "1") (pinfunction "VCCA_1") (pintype "power_in"))
    )
    (net (code "42") (name "2V5") (class "Default")
      (node (ref "C719") (pin "2") (pinfunction "2_2") (pintype "passive"))
      (node (ref "C723") (pin "2") (pinfunction "2_2") (pintype "passive"))
      (node (ref "C729") (pin "2") (pinfunction "2_2") (pintype "passive"))
      (node (ref "R419") (pin "2") (pinfunction "2_2") (pintype "passive"))
      (node (ref "R438") (pin "2") (pinfunction "2_2") (pintype "passive"))
      (node (ref "U67") (pin "1") (pinfunction "VCCO_1") (pintype "power_in"))
      (node (ref "U69") (pin "1") (pinfunction "VCCO_1") (pintype "power_in"))
      (node (ref "U72") (pin "6") (pinfunction "VDD_6") (pintype "power_in"))
    )
    (net (code "43") (name "3V3") (class "Default")
      (node (ref "C727") (pin "2") (pinfunction "2_2") (pintype "passive"))
      (node (ref "F9") (pin "2") (pinfunction "2_2") (pintype "passive"))
      (node (ref "R457") (pin "1") (pinfunction "1_1") (pintype "passive"))
      (node (ref "U68") (pin "23") (pinfunction "VCCB_23") (pintype "power_in"))
      (node (ref "U68") (pin "24") (pinfunction "VCCB_24") (pintype "power_in"))
      (node (ref "U71") (pin "1") (pinfunction "VCC_1") (pintype "power_in"))
    )
    (net (code "44") (name "3V3AUX") (class "Default")
      (node (ref "R224") (pin "1") (pinfunction "1_1") (pintype "passive"))
      (node (ref "R288") (pin "2") (pinfunction "2_2") (pintype "passive"))
      (node (ref "R289") (pin "2") (pinfunction "2_2") (pintype "passive"))
      (node (ref "R346") (pin "2") (pinfunction "2_2") (pintype "passive"))
      (node (ref "R453") (pin "1") (pinfunction "1_1") (pintype "passive"))
      (node (ref "R454") (pin "1") (pinfunction "1_1") (pintype "passive"))
      (node (ref "R455") (pin "1") (pinfunction "1_1") (pintype "passive"))
      (node (ref "R456") (pin "1") (pinfunction "1_1") (pintype "passive"))
    )
    (net (code "45") (name "5V") (class "Default")
      (node (ref "C718") (pin "2") (pinfunction "2_2") (pintype "passive"))
      (node (ref "C722") (pin "2") (pinfunction "2_2") (pintype "passive"))
      (node (ref "R420") (pin "1") (pinfunction "1_1") (pintype "passive"))
      (node (ref "R421") (pin "2") (pinfunction "2_2") (pintype "passive"))
      (node (ref "R437") (pin "1") (pinfunction "1_1") (pintype "passive"))
      (node (ref "R439") (pin "1") (pinfunction "1_1") (pintype "passive"))
      (node (ref "R440") (pin "2") (pinfunction "2_2") (pintype "passive"))
      (node (ref "R444") (pin "1") (pinfunction "1_1") (pintype "passive"))
      (node (ref "R446") (pin "2") (pinfunction "2_2") (pintype "passive"))
      (node (ref "SP3") (pin "4") (pinfunction "VCC_4") (pintype "power_in"))
      (node (ref "U67") (pin "2") (pinfunction "VCCI_2") (pintype "power_in"))
      (node (ref "U69") (pin "2") (pinfunction "VCCI_2") (pintype "power_in"))
    )
    (net (code "46") (name "5VAUX") (class "Default")
      (node (ref "F5") (pin "1") (pinfunction "1_1") (pintype "passive"))
      (node (ref "R449") (pin "1") (pinfunction "1_1") (pintype "passive"))
      (node (ref "R451") (pin "2") (pinfunction "2_2") (pintype "passive"))
    )
    (net (code "47") (name "12V") (class "Default")
      (node (ref "C728") (pin "2") (pinfunction "2_2") (pintype "passive"))
      (node (ref "U70") (pin "7") (pinfunction "VS+_7") (pintype "power_in"))
    )
    (net (code "48") (name "GND") (class "Default")
      (node (ref "C485") (pin "1") (pinfunction "1_1") (pintype "passive"))
      (node (ref "C718") (pin "1") (pinfunction "1_1") (pintype "passive"))
      (node (ref "C719") (pin "1") (pinfunction "1_1") (pintype "passive"))
      (node (ref "C721") (pin "1") (pinfunction "1_1") (pintype "passive"))
      (node (ref "C722") (pin "1") (pinfunction "1_1") (pintype "passive"))
      (node (ref "C723") (pin "1") (pinfunction "1_1") (pintype "passive"))
      (node (ref "C725") (pin "1") (pinfunction "1_1") (pintype "passive"))
      (node (ref "C726") (pin "1") (pinfunction "1_1") (pintype "passive"))
      (node (ref "C727") (pin "1") (pinfunction "1_1") (pintype "passive"))
      (node (ref "C728") (pin "1") (pinfunction "1_1") (pintype "passive"))
      (node (ref "C729") (pin "1") (pinfunction "1_1") (pintype "passive"))
      (node (ref "DS15") (pin "1") (pinfunction "K_1") (pintype "passive"))
      (node (ref "DS16") (pin "1") (pinfunction "K_1") (pintype "passive"))
      (node (ref "DS17") (pin "1") (pinfunction "K_1") (pintype "passive"))
      (node (ref "DS18") (pin "1") (pinfunction "K_1") (pintype "passive"))
      (node (ref "DS19") (pin "1") (pinfunction "K_1") (pintype "passive"))
      (node (ref "DS20") (pin "1") (pinfunction "K_1") (pintype "passive"))
      (node (ref "DS21") (pin "1") (pinfunction "K_1") (pintype "passive"))
      (node (ref "DS22") (pin "1") (pinfunction "K_1") (pintype "passive"))
      (node (ref "DS24") (pin "1") (pinfunction "K_1") (pintype "passive"))
      (node (ref "DS25") (pin "1") (pinfunction "K_1") (pintype "passive"))
      (node (ref "J10") (pin "2") (pinfunction "SH_2") (pintype "passive"))
      (node (ref "J10") (pin "3") (pinfunction "SH_3") (pintype "passive"))
      (node (ref "J10") (pin "4") (pinfunction "SH_4") (pintype "passive"))
      (node (ref "J10") (pin "5") (pinfunction "SH_5") (pintype "passive"))
      (node (ref "J11") (pin "2") (pinfunction "SH_2") (pintype "passive"))
      (node (ref "J11") (pin "3") (pinfunction "SH_3") (pintype "passive"))
      (node (ref "J11") (pin "4") (pinfunction "SH_4") (pintype "passive"))
      (node (ref "J11") (pin "5") (pinfunction "SH_5") (pintype "passive"))
      (node (ref "J9") (pin "2") (pinfunction "SH_2") (pintype "passive"))
      (node (ref "J9") (pin "3") (pinfunction "SH_3") (pintype "passive"))
      (node (ref "J9") (pin "4") (pinfunction "SH_4") (pintype "passive"))
      (node (ref "J9") (pin "5") (pinfunction "SH_5") (pintype "passive"))
      (node (ref "P13") (pin "10") (pinfunction "10_10") (pintype "passive"))
      (node (ref "P13") (pin "12") (pinfunction "12_12") (pintype "passive"))
      (node (ref "P13") (pin "14") (pinfunction "14_14") (pintype "passive"))
      (node (ref "P13") (pin "16") (pinfunction "16_16") (pintype "passive"))
      (node (ref "P13") (pin "18") (pinfunction "18_18") (pintype "passive"))
      (node (ref "P13") (pin "2") (pinfunction "2_2") (pintype "passive"))
      (node (ref "P13") (pin "20") (pinfunction "20_20") (pintype "passive"))
      (node (ref "P13") (pin "4") (pinfunction "4_4") (pintype "passive"))
      (node (ref "P13") (pin "6") (pinfunction "6_6") (pintype "passive"))
      (node (ref "P13") (pin "8") (pinfunction "8_8") (pintype "passive"))
      (node (ref "P14") (pin "10") (pinfunction "10_10") (pintype "passive"))
      (node (ref "P14") (pin "6") (pinfunction "6_6") (pintype "passive"))
      (node (ref "P14") (pin "7") (pinfunction "7_7") (pintype "passive"))
      (node (ref "P14") (pin "8") (pinfunction "8_8") (pintype "passive"))
      (node (ref "P14") (pin "9") (pinfunction "9_9") (pintype "passive"))
      (node (ref "P15") (pin "10") (pinfunction "10_10") (pintype "passive"))
      (node (ref "P15") (pin "12") (pinfunction "12_12") (pintype "passive"))
      (node (ref "P15") (pin "14") (pinfunction "14_14") (pintype "passive"))
      (node (ref "P15") (pin "16") (pinfunction "16_16") (pintype "passive"))
      (node (ref "P15") (pin "18") (pinfunction "18_18") (pintype "passive"))
      (node (ref "P15") (pin "2") (pinfunction "2_2") (pintype "passive"))
      (node (ref "P15") (pin "20") (pinfunction "20_20") (pintype "passive"))
      (node (ref "P15") (pin "4") (pinfunction "4_4") (pintype "passive"))
      (node (ref "P15") (pin "6") (pinfunction "6_6") (pintype "passive"))
      (node (ref "P15") (pin "8") (pinfunction "8_8") (pintype "passive"))
      (node (ref "P16") (pin "14") (pinfunction "14_14") (pintype "passive"))
      (node (ref "P16") (pin "3") (pinfunction "3_3") (pintype "passive"))
      (node (ref "Q12") (pin "2") (pinfunction "S_2") (pintype "passive"))
      (node (ref "Q13") (pin "2") (pinfunction "S_2") (pintype "passive"))
      (node (ref "Q14") (pin "2") (pinfunction "S_2") (pintype "passive"))
      (node (ref "Q15") (pin "2") (pinfunction "S_2") (pintype "passive"))
      (node (ref "Q17") (pin "2") (pinfunction "S_2") (pintype "passive"))
      (node (ref "R225") (pin "1") (pinfunction "1_1") (pintype "passive"))
      (node (ref "R427") (pin "2") (pinfunction "2_2") (pintype "passive"))
      (node (ref "R428") (pin "1") (pinfunction "1_1") (pintype "passive"))
      (node (ref "R429") (pin "1") (pinfunction "1_1") (pintype "passive"))
      (node (ref "R436") (pin "1") (pinfunction "1_1") (pintype "passive"))
      (node (ref "R442") (pin "2") (pinfunction "2_2") (pintype "passive"))
      (node (ref "R443") (pin "1") (pinfunction "1_1") (pintype "passive"))
      (node (ref "R445") (pin "1") (pinfunction "1_1") (pintype "passive"))
      (node (ref "R448") (pin "1") (pinfunction "1_1") (pintype "passive"))
      (node (ref "R452") (pin "1") (pinfunction "1_1") (pintype "passive"))
      (node (ref "R458") (pin "1") (pinfunction "1_1") (pintype "passive"))
      (node (ref "R460") (pin "1") (pinfunction "1_1") (pintype "passive"))
      (node (ref "S4") (pin "2") (pinfunction "2_2") (pintype "output"))
      (node (ref "S5") (pin "2") (pinfunction "2_2") (pintype "output"))
      (node (ref "SP25") (pin "1") (pinfunction "A_1") (pintype "passive"))
      (node (ref "SP26") (pin "1") (pinfunction "A_1") (pintype "passive"))
      (node (ref "SP27") (pin "1") (pinfunction "A_1") (pintype "passive"))
      (node (ref "SP28") (pin "1") (pinfunction "A_1") (pintype "passive"))
      (node (ref "SP29") (pin "1") (pinfunction "A_1") (pintype "passive"))
      (node (ref "SP3") (pin "1") (pinfunction "GND_1") (pintype "power_in"))
      (node (ref "SP30") (pin "1") (pinfunction "A_1") (pintype "passive"))
      (node (ref "SP31") (pin "1") (pinfunction "A_1") (pintype "passive"))
      (node (ref "SP32") (pin "1") (pinfunction "A_1") (pintype "passive"))
      (node (ref "SP33") (pin "1") (pinfunction "A_1") (pintype "passive"))
      (node (ref "SP34") (pin "1") (pinfunction "A_1") (pintype "passive"))
      (node (ref "SP35") (pin "1") (pinfunction "A_1") (pintype "passive"))
      (node (ref "SP36") (pin "1") (pinfunction "A_1") (pintype "passive"))
      (node (ref "SP37") (pin "1") (pinfunction "A_1") (pintype "passive"))
      (node (ref "SP38") (pin "1") (pinfunction "A_1") (pintype "passive"))
      (node (ref "SP39") (pin "1") (pinfunction "A_1") (pintype "passive"))
      (node (ref "SP40") (pin "1") (pinfunction "A_1") (pintype "passive"))
      (node (ref "SP41") (pin "1") (pinfunction "A_1") (pintype "passive"))
      (node (ref "SP42") (pin "2") (pinfunction "B_2") (pintype "passive"))
      (node (ref "SP43") (pin "1") (pinfunction "A_1") (pintype "passive"))
      (node (ref "SP44") (pin "1") (pinfunction "A_1") (pintype "passive"))
      (node (ref "SP45") (pin "1") (pinfunction "A_1") (pintype "passive"))
      (node (ref "SP46") (pin "1") (pinfunction "A_1") (pintype "passive"))
      (node (ref "U67") (pin "11") (pinfunction "VEE_11") (pintype "power_in"))
      (node (ref "U67") (pin "13") (pinfunction "PAD_13") (pintype "power_in"))
      (node (ref "U67") (pin "3") (pinfunction "VEE_3") (pintype "power_in"))
      (node (ref "U67") (pin "5") (pinfunction "VEE_5") (pintype "power_in"))
      (node (ref "U67") (pin "9") (pinfunction "VEE_9") (pintype "power_in"))
      (node (ref "U68") (pin "11") (pinfunction "GND_11") (pintype "power_in"))
      (node (ref "U68") (pin "12") (pinfunction "GND_12") (pintype "power_in"))
      (node (ref "U68") (pin "13") (pinfunction "GND_13") (pintype "power_in"))
      (node (ref "U69") (pin "11") (pinfunction "VEE_11") (pintype "power_in"))
      (node (ref "U69") (pin "13") (pinfunction "PAD_13") (pintype "power_in"))
      (node (ref "U69") (pin "3") (pinfunction "VEE_3") (pintype "power_in"))
      (node (ref "U69") (pin "5") (pinfunction "VEE_5") (pintype "power_in"))
      (node (ref "U69") (pin "9") (pinfunction "VEE_9") (pintype "power_in"))
      (node (ref "U70") (pin "9") (pinfunction "TH_9") (pintype "passive"))
      (node (ref "U71") (pin "2") (pinfunction "GND_2") (pintype "power_in"))
      (node (ref "U72") (pin "3") (pinfunction "GND_3") (pintype "power_in"))
    )
    (net (code "49") (name "N12V") (class "Default")
      (node (ref "C485") (pin "2") (pinfunction "2_2") (pintype "passive"))
      (node (ref "U70") (pin "4") (pinfunction "VS-_4") (pintype "power_in"))
    )
    (net (code "50") (name "Net-(DS15-A)") (class "Default")
      (node (ref "DS15") (pin "2") (pinfunction "A_2") (pintype "passive"))
      (node (ref "R423") (pin "1") (pinfunction "1_1") (pintype "passive"))
    )
    (net (code "51") (name "Net-(DS16-A)") (class "Default")
      (node (ref "DS16") (pin "2") (pinfunction "A_2") (pintype "passive"))
      (node (ref "R422") (pin "1") (pinfunction "1_1") (pintype "passive"))
    )
    (net (code "52") (name "Net-(DS17-A)") (class "Default")
      (node (ref "DS17") (pin "2") (pinfunction "A_2") (pintype "passive"))
      (node (ref "R424") (pin "1") (pinfunction "1_1") (pintype "passive"))
    )
    (net (code "53") (name "Net-(DS18-A)") (class "Default")
      (node (ref "DS18") (pin "2") (pinfunction "A_2") (pintype "passive"))
      (node (ref "R425") (pin "1") (pinfunction "1_1") (pintype "passive"))
    )
    (net (code "54") (name "Net-(DS19-A)") (class "Default")
      (node (ref "DS19") (pin "2") (pinfunction "A_2") (pintype "passive"))
      (node (ref "R432") (pin "2") (pinfunction "2_2") (pintype "passive"))
    )
    (net (code "55") (name "Net-(DS20-A)") (class "Default")
      (node (ref "DS20") (pin "2") (pinfunction "A_2") (pintype "passive"))
      (node (ref "R433") (pin "2") (pinfunction "2_2") (pintype "passive"))
    )
    (net (code "56") (name "Net-(DS21-A)") (class "Default")
      (node (ref "DS21") (pin "2") (pinfunction "A_2") (pintype "passive"))
      (node (ref "R434") (pin "2") (pinfunction "2_2") (pintype "passive"))
    )
    (net (code "57") (name "Net-(DS22-A)") (class "Default")
      (node (ref "DS22") (pin "2") (pinfunction "A_2") (pintype "passive"))
      (node (ref "R431") (pin "2") (pinfunction "2_2") (pintype "passive"))
    )
    (net (code "58") (name "Net-(DS23-A)") (class "Default")
      (node (ref "DS23") (pin "2") (pinfunction "A_2") (pintype "passive"))
      (node (ref "R437") (pin "2") (pinfunction "2_2") (pintype "passive"))
    )
    (net (code "59") (name "Net-(DS24-A)") (class "Default")
      (node (ref "DS24") (pin "2") (pinfunction "A_2") (pintype "passive"))
      (node (ref "R444") (pin "2") (pinfunction "2_2") (pintype "passive"))
    )
    (net (code "60") (name "Net-(DS25-A)") (class "Default")
      (node (ref "DS25") (pin "2") (pinfunction "A_2") (pintype "passive"))
      (node (ref "R449") (pin "2") (pinfunction "2_2") (pintype "passive"))
    )
    (net (code "61") (name "Net-(DS26-A)") (class "Default")
      (node (ref "DS26") (pin "2") (pinfunction "A_2") (pintype "passive"))
      (node (ref "R457") (pin "2") (pinfunction "2_2") (pintype "passive"))
    )
    (net (code "62") (name "Net-(DS27-A)") (class "Default")
      (node (ref "DS27") (pin "2") (pinfunction "A_2") (pintype "passive"))
      (node (ref "R224") (pin "2") (pinfunction "2_2") (pintype "passive"))
    )
    (net (code "63") (name "Net-(F5-Pad2)") (class "Default")
      (node (ref "F5") (pin "2") (pinfunction "2_2") (pintype "passive"))
      (node (ref "P13") (pin "19") (pinfunction "19_19") (pintype "passive"))
      (node (ref "P15") (pin "19") (pinfunction "19_19") (pintype "passive"))
    )
    (net (code "64") (name "Net-(F8-Pad2)") (class "Default")
      (node (ref "F8") (pin "2") (pinfunction "2_2") (pintype "passive"))
      (node (ref "P13") (pin "1") (pinfunction "1_1") (pintype "passive"))
      (node (ref "P15") (pin "1") (pinfunction "1_1") (pintype "passive"))
    )
    (net (code "65") (name "Net-(F9-Pad1)") (class "Default")
      (node (ref "F9") (pin "1") (pinfunction "1_1") (pintype "passive"))
      (node (ref "P14") (pin "1") (pinfunction "1_1") (pintype "passive"))
    )
    (net (code "66") (name "Net-(J9-IN)") (class "Default")
      (node (ref "C720") (pin "2") (pinfunction "2_2") (pintype "passive"))
      (node (ref "J9") (pin "1") (pinfunction "IN_1") (pintype "passive"))
      (node (ref "R426") (pin "1") (pinfunction "1_1") (pintype "passive"))
      (node (ref "SP3") (pin "3") (pinfunction "IO2_3") (pintype "power_in"))
    )
    (net (code "67") (name "Net-(J10-IN)") (class "Default")
      (node (ref "C724") (pin "2") (pinfunction "2_2") (pintype "passive"))
      (node (ref "J10") (pin "1") (pinfunction "IN_1") (pintype "passive"))
      (node (ref "R441") (pin "1") (pinfunction "1_1") (pintype "passive"))
      (node (ref "SP3") (pin "2") (pinfunction "IO1_2") (pintype "power_in"))
    )
    (net (code "68") (name "Net-(J11-IN)") (class "Default")
      (node (ref "J11") (pin "1") (pinfunction "IN_1") (pintype "passive"))
      (node (ref "R447") (pin "2") (pinfunction "2_2") (pintype "passive"))
      (node (ref "SP42") (pin "1") (pinfunction "A_1") (pintype "passive"))
    )
    (net (code "69") (name "Net-(P16-Pad2)") (class "Default")
      (node (ref "P16") (pin "2") (pinfunction "2_2") (pintype "passive"))
      (node (ref "R455") (pin "2") (pinfunction "2_2") (pintype "passive"))
    )
    (net (code "70") (name "Net-(P16-Pad5)") (class "Default")
      (node (ref "P16") (pin "5") (pinfunction "5_5") (pintype "passive"))
      (node (ref "R454") (pin "2") (pinfunction "2_2") (pintype "passive"))
    )
    (net (code "71") (name "Net-(P16-Pad6)") (class "Default")
      (node (ref "P16") (pin "6") (pinfunction "6_6") (pintype "passive"))
      (node (ref "R456") (pin "2") (pinfunction "2_2") (pintype "passive"))
    )
    (net (code "72") (name "Net-(P16-Pad11)") (class "Default")
      (node (ref "P16") (pin "11") (pinfunction "11_11") (pintype "passive"))
      (node (ref "R453") (pin "2") (pinfunction "2_2") (pintype "passive"))
    )
    (net (code "73") (name "Net-(Q15-G)") (class "Default")
      (node (ref "Q15") (pin "1") (pinfunction "G_1") (pintype "passive"))
      (node (ref "Q17") (pin "3") (pinfunction "D_3") (pintype "passive"))
      (node (ref "R289") (pin "1") (pinfunction "1_1") (pintype "passive"))
    )
    (net (code "74") (name "Net-(U67-LE{slash}HYS)") (class "Default")
      (node (ref "R429") (pin "2") (pinfunction "2_2") (pintype "passive"))
      (node (ref "U67") (pin "8") (pinfunction "LE/HYS_8") (pintype "input"))
    )
    (net (code "75") (name "Net-(U67-SDN)") (class "Default")
      (node (ref "R419") (pin "1") (pinfunction "1_1") (pintype "passive"))
      (node (ref "U67") (pin "7") (pinfunction "SDN_7") (pintype "input"))
    )
    (net (code "76") (name "Net-(U67-VN)") (class "Default")
      (node (ref "C721") (pin "2") (pinfunction "2_2") (pintype "passive"))
      (node (ref "R421") (pin "1") (pinfunction "1_1") (pintype "passive"))
      (node (ref "R428") (pin "2") (pinfunction "2_2") (pintype "passive"))
      (node (ref "U67") (pin "6") (pinfunction "VN_6") (pintype "input"))
    )
    (net (code "77") (name "Net-(U67-VP)") (class "Default")
      (node (ref "C720") (pin "1") (pinfunction "1_1") (pintype "passive"))
      (node (ref "R420") (pin "2") (pinfunction "2_2") (pintype "passive"))
      (node (ref "R426") (pin "2") (pinfunction "2_2") (pintype "passive"))
      (node (ref "R427") (pin "1") (pinfunction "1_1") (pintype "passive"))
      (node (ref "U67") (pin "4") (pinfunction "VP_4") (pintype "input"))
    )
    (net (code "78") (name "Net-(U68-B1)") (class "Default")
      (node (ref "R431") (pin "1") (pinfunction "1_1") (pintype "passive"))
      (node (ref "U68") (pin "21") (pinfunction "B1_21") (pintype "bidirectional"))
    )
    (net (code "79") (name "Net-(U68-B2)") (class "Default")
      (node (ref "R432") (pin "1") (pinfunction "1_1") (pintype "passive"))
      (node (ref "U68") (pin "20") (pinfunction "B2_20") (pintype "bidirectional"))
    )
    (net (code "80") (name "Net-(U68-B3)") (class "Default")
      (node (ref "R433") (pin "1") (pinfunction "1_1") (pintype "passive"))
      (node (ref "U68") (pin "19") (pinfunction "B3_19") (pintype "bidirectional"))
    )
    (net (code "81") (name "Net-(U68-B4)") (class "Default")
      (node (ref "R434") (pin "1") (pinfunction "1_1") (pintype "passive"))
      (node (ref "U68") (pin "18") (pinfunction "B4_18") (pintype "bidirectional"))
    )
    (net (code "82") (name "Net-(U68-B5)") (class "Default")
      (node (ref "R425") (pin "2") (pinfunction "2_2") (pintype "passive"))
      (node (ref "U68") (pin "17") (pinfunction "B5_17") (pintype "bidirectional"))
    )
    (net (code "83") (name "Net-(U68-B6)") (class "Default")
      (node (ref "R424") (pin "2") (pinfunction "2_2") (pintype "passive"))
      (node (ref "U68") (pin "16") (pinfunction "B6_16") (pintype "bidirectional"))
    )
    (net (code "84") (name "Net-(U68-B7)") (class "Default")
      (node (ref "R422") (pin "2") (pinfunction "2_2") (pintype "passive"))
      (node (ref "U68") (pin "15") (pinfunction "B7_15") (pintype "bidirectional"))
    )
    (net (code "85") (name "Net-(U68-B8)") (class "Default")
      (node (ref "R423") (pin "2") (pinfunction "2_2") (pintype "passive"))
      (node (ref "U68") (pin "14") (pinfunction "B8_14") (pintype "bidirectional"))
    )
    (net (code "86") (name "Net-(U68-DIR)") (class "Default")
      (node (ref "R435") (pin "1") (pinfunction "1_1") (pintype "passive"))
      (node (ref "U68") (pin "2") (pinfunction "DIR_2") (pintype "bidirectional"))
    )
    (net (code "87") (name "Net-(U68-OEn)") (class "Default")
      (node (ref "R430") (pin "1") (pinfunction "1_1") (pintype "passive"))
      (node (ref "R436") (pin "2") (pinfunction "2_2") (pintype "passive"))
      (node (ref "U68") (pin "22") (pinfunction "OEn_22") (pintype "bidirectional"))
    )
    (net (code "88") (name "Net-(U69-LE{slash}HYS)") (class "Default")
      (node (ref "R445") (pin "2") (pinfunction "2_2") (pintype "passive"))
      (node (ref "U69") (pin "8") (pinfunction "LE/HYS_8") (pintype "input"))
    )
    (net (code "89") (name "Net-(U69-SDN)") (class "Default")
      (node (ref "R438") (pin "1") (pinfunction "1_1") (pintype "passive"))
      (node (ref "U69") (pin "7") (pinfunction "SDN_7") (pintype "input"))
    )
    (net (code "90") (name "Net-(U69-VN)") (class "Default")
      (node (ref "C725") (pin "2") (pinfunction "2_2") (pintype "passive"))
      (node (ref "R440") (pin "1") (pinfunction "1_1") (pintype "passive"))
      (node (ref "R443") (pin "2") (pinfunction "2_2") (pintype "passive"))
      (node (ref "U69") (pin "6") (pinfunction "VN_6") (pintype "input"))
    )
    (net (code "91") (name "Net-(U69-VP)") (class "Default")
      (node (ref "C724") (pin "1") (pinfunction "1_1") (pintype "passive"))
      (node (ref "R439") (pin "2") (pinfunction "2_2") (pintype "passive"))
      (node (ref "R441") (pin "2") (pinfunction "2_2") (pintype "passive"))
      (node (ref "R442") (pin "1") (pinfunction "1_1") (pintype "passive"))
      (node (ref "U69") (pin "4") (pinfunction "VP_4") (pintype "input"))
    )
    (net (code "92") (name "Net-(U70-VIN+)") (class "Default")
      (node (ref "U70") (pin "3") (pinfunction "VIN+_3") (pintype "input"))
      (node (ref "U71") (pin "5") (pinfunction "R_5") (pintype "output"))
    )
    (net (code "93") (name "Net-(U70-VIN-)") (class "Default")
      (node (ref "C726") (pin "2") (pinfunction "2_2") (pintype "passive"))
      (node (ref "R450") (pin "1") (pinfunction "1_1") (pintype "passive"))
      (node (ref "R452") (pin "2") (pinfunction "2_2") (pintype "passive"))
      (node (ref "U70") (pin "2") (pinfunction "VIN-_2") (pintype "input"))
    )
    (net (code "94") (name "Net-(U70-VOUT)") (class "Default")
      (node (ref "R447") (pin "1") (pinfunction "1_1") (pintype "passive"))
      (node (ref "R450") (pin "2") (pinfunction "2_2") (pintype "passive"))
      (node (ref "U70") (pin "6") (pinfunction "VOUT_6") (pintype "output"))
    )
    (net (code "95") (name "unconnected-(P16-Pad7)") (class "Default")
      (node (ref "P16") (pin "7") (pinfunction "7_7") (pintype "passive+no_connect"))
    )
    (net (code "96") (name "unconnected-(P16-Pad10)") (class "Default")
      (node (ref "P16") (pin "10") (pinfunction "10_10") (pintype "passive+no_connect"))
    )
    (net (code "97") (name "unconnected-(S4-Pad3)") (class "Default")
      (node (ref "S4") (pin "3") (pinfunction "3_3") (pintype "output+no_connect"))
    )
    (net (code "98") (name "unconnected-(S4-Pad4)") (class "Default")
      (node (ref "S4") (pin "4") (pinfunction "4_4") (pintype "output+no_connect"))
    )
    (net (code "99") (name "unconnected-(S5-Pad3)") (class "Default")
      (node (ref "S5") (pin "3") (pinfunction "3_3") (pintype "output+no_connect"))
    )
    (net (code "100") (name "unconnected-(S5-Pad4)") (class "Default")
      (node (ref "S5") (pin "4") (pinfunction "4_4") (pintype "output+no_connect"))
    )
    (net (code "101") (name "unconnected-(U70-NC-Pad1)") (class "Default")
      (node (ref "U70") (pin "1") (pinfunction "NC_1") (pintype "passive+no_connect"))
    )
    (net (code "102") (name "unconnected-(U70-NC-Pad5)") (class "Default")
      (node (ref "U70") (pin "5") (pinfunction "NC_5") (pintype "passive+no_connect"))
    )
    (net (code "103") (name "unconnected-(U70-NC-Pad8)") (class "Default")
      (node (ref "U70") (pin "8") (pinfunction "NC_8") (pintype "passive+no_connect"))
    )
    (net (code "104") (name "unconnected-(U72-E{slash}D-Pad1)") (class "Default")
      (node (ref "U72") (pin "1") (pinfunction "E/D_1") (pintype "input+no_connect"))
    )
    (net (code "105") (name "unconnected-(U72-NC-Pad2)") (class "Default")
      (node (ref "U72") (pin "2") (pinfunction "NC_2") (pintype "passive+no_connect"))
    )
  )
)
